# touchwheel0.net
KiCad netlist of a schematic drawn in EAGLE
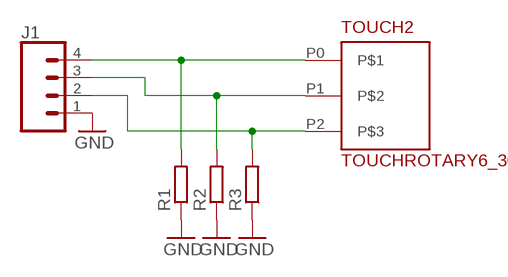
[diagram p0: schematic, sheet 1]

(export (version "E")
  (design (tool "Eeschema 10.0.6"))
  (components
    (comp (ref "J1")
      (value "CONN_04")
      (footprint "eagle-import:1X04")
      (libsource (lib "eagle-import") (part "CONN_04"))
    )
    (comp (ref "R1")
      (value "R-EU_R0805")
      (footprint "eagle-import:R0805")
      (libsource (lib "eagle-import") (part "R-EU_R0805"))
    )
    (comp (ref "R2")
      (value "R-EU_R0805")
      (footprint "eagle-import:R0805")
      (libsource (lib "eagle-import") (part "R-EU_R0805"))
    )
    (comp (ref "R3")
      (value "R-EU_R0805")
      (footprint "eagle-import:R0805")
      (libsource (lib "eagle-import") (part "R-EU_R0805"))
    )
    (comp (ref "TOUCH2")
      (value "TOUCHROTARY6_30")
      (footprint "eagle-import:TOUCHROTARY1B")
      (libsource (lib "eagle-import") (part "TOUCHROTARY6_30"))
    )
  )
  (nets
    (net (code "1") (name "GND") (class "Default")
      (node (ref "J1") (pin "1") (pinfunction "1_1") (pintype "passive"))
      (node (ref "R1") (pin "1") (pinfunction "1_1") (pintype "passive"))
      (node (ref "R2") (pin "1") (pinfunction "1_1") (pintype "passive"))
      (node (ref "R3") (pin "1") (pinfunction "1_1") (pintype "passive"))
    )
    (net (code "2") (name "Net-(TOUCH2-P$1)") (class "Default")
      (node (ref "J1") (pin "4") (pinfunction "4_4") (pintype "passive"))
      (node (ref "R1") (pin "2") (pinfunction "2_2") (pintype "passive"))
      (node (ref "TOUCH2") (pin "P0") (pinfunction "P$1_P0") (pintype "bidirectional"))
    )
    (net (code "3") (name "Net-(TOUCH2-P$2)") (class "Default")
      (node (ref "J1") (pin "3") (pinfunction "3_3") (pintype "passive"))
      (node (ref "R2") (pin "2") (pinfunction "2_2") (pintype "passive"))
      (node (ref "TOUCH2") (pin "P1") (pinfunction "P$2_P1") (pintype "bidirectional"))
    )
    (net (code "4") (name "Net-(TOUCH2-P$3)") (class "Default")
      (node (ref "J1") (pin "2") (pinfunction "2_2") (pintype "passive"))
      (node (ref "R3") (pin "2") (pinfunction "2_2") (pintype "passive"))
      (node (ref "TOUCH2") (pin "P2") (pinfunction "P$3_P2") (pintype "bidirectional"))
    )
  )
)
